# Dev_BRD_ATTINY1616.net
KiCad netlist of a schematic drawn in Altium Designer
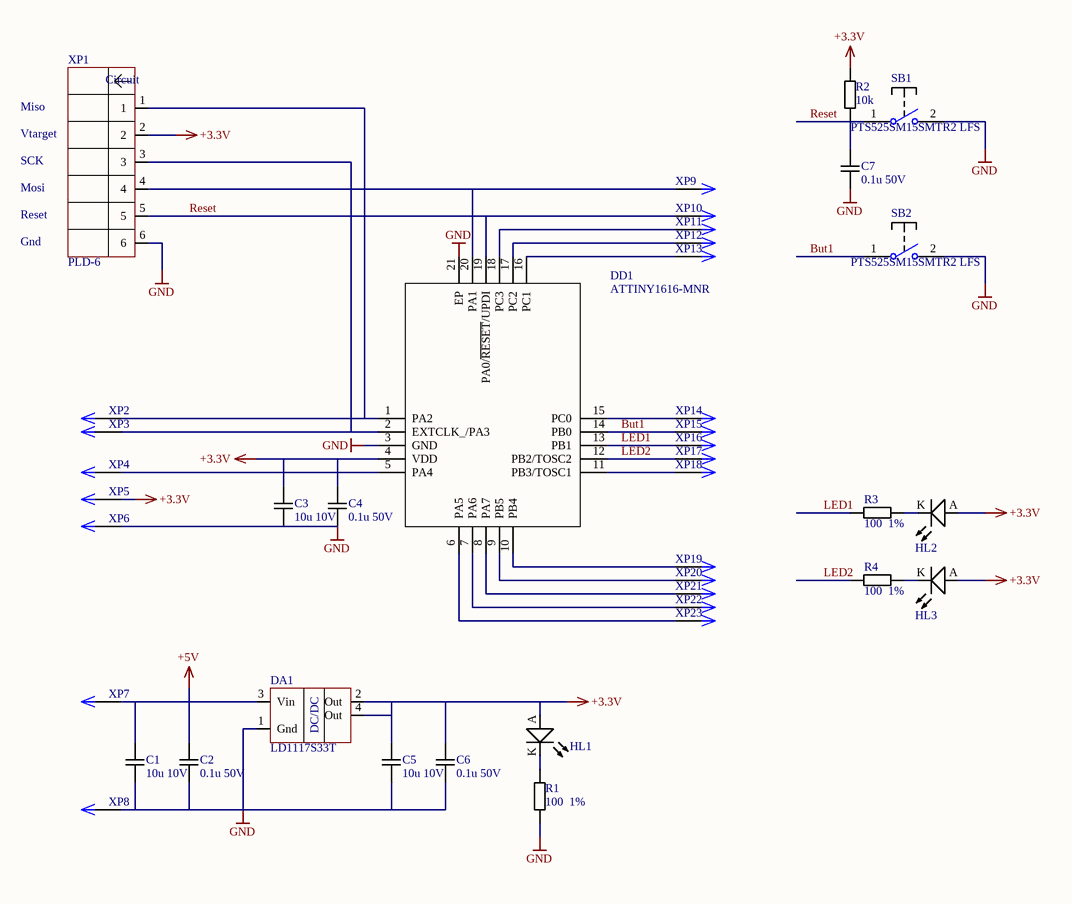
[diagram p0: Dev_BRD_ATTINY1616.SchDoc]

(export (version "E")
  (design (tool "Eeschema 10.0.6"))
  (components
    (comp (ref "C1")
      (value "10u 10V")
      (footprint "CAPC1608(0603)N")
      (description "10uF 0603 10V X5R  10%")
      (fields
        (field (name "PART NUMBER") "GRM188R61A106KE69J")
        (field (name "MOUSER PART NUMBER") "81-GRM188R61A106KE9J")
      )
      (libsource (lib "SssAccesDatbase") (part "Cap"))
    )
    (comp (ref "C2")
      (value "0.1u 50V")
      (footprint "CAPC1608(0603)N")
      (description "0,1uF 0603 50V X7R  +/-20%")
      (fields
        (field (name "PART NUMBER") "UMF107B7104MAHT")
        (field (name "MOUSER PART NUMBER") "963-UMF107B7104MAHT")
      )
      (libsource (lib "SssAccesDatbase") (part "Cap"))
    )
    (comp (ref "C3")
      (value "10u 10V")
      (footprint "CAPC1608(0603)N")
      (description "10uF 0603 10V X5R  10%")
      (fields
        (field (name "PART NUMBER") "GRM188R61A106KE69J")
        (field (name "MOUSER PART NUMBER") "81-GRM188R61A106KE9J")
      )
      (libsource (lib "SssAccesDatbase") (part "Cap"))
    )
    (comp (ref "C4")
      (value "0.1u 50V")
      (footprint "CAPC1608(0603)N")
      (description "0,1uF 0603 50V X7R  +/-20%")
      (fields
        (field (name "PART NUMBER") "UMF107B7104MAHT")
        (field (name "MOUSER PART NUMBER") "963-UMF107B7104MAHT")
      )
      (libsource (lib "SssAccesDatbase") (part "Cap"))
    )
    (comp (ref "C5")
      (value "10u 10V")
      (footprint "CAPC1608(0603)N")
      (description "10uF 0603 10V X5R  10%")
      (fields
        (field (name "PART NUMBER") "GRM188R61A106KE69J")
        (field (name "MOUSER PART NUMBER") "81-GRM188R61A106KE9J")
      )
      (libsource (lib "SssAccesDatbase") (part "Cap"))
    )
    (comp (ref "C6")
      (value "0.1u 50V")
      (footprint "CAPC1608(0603)N")
      (description "0,1uF 0603 50V X7R  +/-20%")
      (fields
        (field (name "PART NUMBER") "UMF107B7104MAHT")
        (field (name "MOUSER PART NUMBER") "963-UMF107B7104MAHT")
      )
      (libsource (lib "SssAccesDatbase") (part "Cap"))
    )
    (comp (ref "C7")
      (value "0.1u 50V")
      (footprint "CAPC1608(0603)N")
      (description "0,1uF 0603 50V X7R  +/-20%")
      (fields
        (field (name "PART NUMBER") "UMF107B7104MAHT")
        (field (name "MOUSER PART NUMBER") "963-UMF107B7104MAHT")
      )
      (libsource (lib "SssAccesDatbase") (part "Cap"))
    )
    (comp (ref "DA1")
      (value "LD1117S33T")
      (footprint "SOT223_M")
      (description "LDO Voltage Regulators 3.3V 0.8A Positive")
      (libsource (lib "SssAccesDatbase") (part "LD1117S33T"))
    )
    (comp (ref "DD1")
      (value "ATTINY1616-MNR")
      (footprint "QFN40P300X300X90-21N")
      (description "AVR tinyAVR™ 1 Microcontroller IC 8-Bit 20MHz 16KB (16K x 8) FLASH 20-VQFN (3x3)")
      (fields
        (field (name "MOUSER PART NUMBER") "556-ATTINY1616MNR")
        (field (name "DIGI-KEY PART NUMBER") "ATTINY1616-MNRCT-ND")
      )
      (libsource (lib "SssAccesDatbase") (part "ATTINY1616-MNR_1"))
    )
    (comp (ref "HL1")
      (value "Bl 0603")
      (footprint "LED-0603-BLUE")
      (description "LED BLUE DIFFUSED 0603 SMD")
      (fields
        (field (name "PART NUMBER") "150060BS55040")
        (field (name "DIGI-KEY PART NUMBER") "732-12013-1-ND")
      )
      (libsource (lib "SssAccesDatbase") (part "LED"))
    )
    (comp (ref "HL2")
      (value "Bl 0603")
      (footprint "LED-0603-BLUE")
      (description "LED BLUE DIFFUSED 0603 SMD")
      (fields
        (field (name "PART NUMBER") "150060BS55040")
        (field (name "DIGI-KEY PART NUMBER") "732-12013-1-ND")
      )
      (libsource (lib "SssAccesDatbase") (part "LED"))
    )
    (comp (ref "HL3")
      (value "Bl 0603")
      (footprint "LED-0603-BLUE")
      (description "LED BLUE DIFFUSED 0603 SMD")
      (fields
        (field (name "PART NUMBER") "150060BS55040")
        (field (name "DIGI-KEY PART NUMBER") "732-12013-1-ND")
      )
      (libsource (lib "SssAccesDatbase") (part "LED"))
    )
    (comp (ref "R1")
      (value "100  1%")
      (footprint "RESC1608(0603)N")
      (description "RES SMD 0603 100  1% 25ppm")
      (fields
        (field (name "PART NUMBER") "RT0603FRD07100RL")
        (field (name "MOUSER PART NUMBER") "603-RT0603FRD07100RL")
      )
      (libsource (lib "") (part "Resistor general_1"))
    )
    (comp (ref "R2")
      (value "10k")
      (footprint "RESC1608(0603)N")
      (description "RES SMD 0603 10k 5% 100ppm")
      (fields
        (field (name "PART NUMBER") "RC0603JR-0710KL")
        (field (name "MOUSER PART NUMBER") "603-RC0603JR-0710KL")
      )
      (libsource (lib "") (part "Resistor general_1"))
    )
    (comp (ref "R3")
      (value "100  1%")
      (footprint "RESC1608(0603)N")
      (description "RES SMD 0603 100  1% 25ppm")
      (fields
        (field (name "PART NUMBER") "RT0603FRD07100RL")
        (field (name "MOUSER PART NUMBER") "603-RT0603FRD07100RL")
      )
      (libsource (lib "SssAccesDatbase") (part "Resistor general"))
    )
    (comp (ref "R4")
      (value "100  1%")
      (footprint "RESC1608(0603)N")
      (description "RES SMD 0603 100  1% 25ppm")
      (fields
        (field (name "PART NUMBER") "RT0603FRD07100RL")
        (field (name "MOUSER PART NUMBER") "603-RT0603FRD07100RL")
      )
      (libsource (lib "SssAccesDatbase") (part "Resistor general"))
    )
    (comp (ref "SB1")
      (value "PTS525SM15SMTR2 LFS")
      (footprint "TACT_SWITCH KPT1187B")
      (description "SWITCH TACTILE SPST-NO 0.02A 15V")
      (fields (field (name "DIGI-KEY PART NUMBER") "CKN9104CT-ND"))
      (libsource (lib "SssAccesDatbase") (part "TACT_SWITCH KPT1187B"))
    )
    (comp (ref "SB2")
      (value "PTS525SM15SMTR2 LFS")
      (footprint "TACT_SWITCH KPT1187B")
      (description "SWITCH TACTILE SPST-NO 0.02A 15V")
      (fields (field (name "DIGI-KEY PART NUMBER") "CKN9104CT-ND"))
      (libsource (lib "SssAccesDatbase") (part "TACT_SWITCH KPT1187B"))
    )
    (comp (ref "XP1")
      (value "PLD-6")
      (footprint "PLD-6-3D")
      (libsource (lib "SssAccesDatbase") (part "XP-6"))
    )
    (comp (ref "XP2")
      (value "PLS-1")
      (footprint "PLS-1-3D")
      (description "CONN HEADER VERT 1POS")
      (fields
        (field (name "DIGI-KEY PART NUMBER") "S1011EC-01-ND")
        (field (name "MANUFACTURER PART NUMBER") "PRPC001SAAN-RC")
      )
      (libsource (lib "SssAccesDatbase") (part "XP-1_1"))
    )
    (comp (ref "XP3")
      (value "PLS-1")
      (footprint "PLS-1-3D")
      (description "CONN HEADER VERT 1POS")
      (fields
        (field (name "DIGI-KEY PART NUMBER") "S1011EC-01-ND")
        (field (name "MANUFACTURER PART NUMBER") "PRPC001SAAN-RC")
      )
      (libsource (lib "SssAccesDatbase") (part "XP-1_1"))
    )
    (comp (ref "XP4")
      (value "PLS-1")
      (footprint "PLS-1-3D")
      (description "CONN HEADER VERT 1POS")
      (fields
        (field (name "DIGI-KEY PART NUMBER") "S1011EC-01-ND")
        (field (name "MANUFACTURER PART NUMBER") "PRPC001SAAN-RC")
      )
      (libsource (lib "SssAccesDatbase") (part "XP-1_1"))
    )
    (comp (ref "XP5")
      (value "PLS-1")
      (footprint "PLS-1-3D")
      (description "CONN HEADER VERT 1POS")
      (fields
        (field (name "DIGI-KEY PART NUMBER") "S1011EC-01-ND")
        (field (name "MANUFACTURER PART NUMBER") "PRPC001SAAN-RC")
      )
      (libsource (lib "SssAccesDatbase") (part "XP-1_1"))
    )
    (comp (ref "XP6")
      (value "PLS-1")
      (footprint "PLS-1-3D")
      (description "CONN HEADER VERT 1POS")
      (fields
        (field (name "DIGI-KEY PART NUMBER") "S1011EC-01-ND")
        (field (name "MANUFACTURER PART NUMBER") "PRPC001SAAN-RC")
      )
      (libsource (lib "SssAccesDatbase") (part "XP-1_1"))
    )
    (comp (ref "XP7")
      (value "PLS-1")
      (footprint "PLS-1-3D")
      (description "CONN HEADER VERT 1POS")
      (fields
        (field (name "DIGI-KEY PART NUMBER") "S1011EC-01-ND")
        (field (name "MANUFACTURER PART NUMBER") "PRPC001SAAN-RC")
      )
      (libsource (lib "SssAccesDatbase") (part "XP-1_1"))
    )
    (comp (ref "XP8")
      (value "PLS-1")
      (footprint "PLS-1-3D")
      (description "CONN HEADER VERT 1POS")
      (fields
        (field (name "DIGI-KEY PART NUMBER") "S1011EC-01-ND")
        (field (name "MANUFACTURER PART NUMBER") "PRPC001SAAN-RC")
      )
      (libsource (lib "SssAccesDatbase") (part "XP-1_1"))
    )
    (comp (ref "XP9")
      (value "PLS-1")
      (footprint "PLS-1-3D")
      (description "CONN HEADER VERT 1POS")
      (fields
        (field (name "DIGI-KEY PART NUMBER") "S1011EC-01-ND")
        (field (name "MANUFACTURER PART NUMBER") "PRPC001SAAN-RC")
      )
      (libsource (lib "SssAccesDatbase") (part "XP-1_1"))
    )
    (comp (ref "XP10")
      (value "PLS-1")
      (footprint "PLS-1-3D")
      (description "CONN HEADER VERT 1POS")
      (fields
        (field (name "DIGI-KEY PART NUMBER") "S1011EC-01-ND")
        (field (name "MANUFACTURER PART NUMBER") "PRPC001SAAN-RC")
      )
      (libsource (lib "SssAccesDatbase") (part "XP-1_1"))
    )
    (comp (ref "XP11")
      (value "PLS-1")
      (footprint "PLS-1-3D")
      (description "CONN HEADER VERT 1POS")
      (fields
        (field (name "DIGI-KEY PART NUMBER") "S1011EC-01-ND")
        (field (name "MANUFACTURER PART NUMBER") "PRPC001SAAN-RC")
      )
      (libsource (lib "SssAccesDatbase") (part "XP-1_1"))
    )
    (comp (ref "XP12")
      (value "PLS-1")
      (footprint "PLS-1-3D")
      (description "CONN HEADER VERT 1POS")
      (fields
        (field (name "DIGI-KEY PART NUMBER") "S1011EC-01-ND")
        (field (name "MANUFACTURER PART NUMBER") "PRPC001SAAN-RC")
      )
      (libsource (lib "SssAccesDatbase") (part "XP-1_1"))
    )
    (comp (ref "XP13")
      (value "PLS-1")
      (footprint "PLS-1-3D")
      (description "CONN HEADER VERT 1POS")
      (fields
        (field (name "DIGI-KEY PART NUMBER") "S1011EC-01-ND")
        (field (name "MANUFACTURER PART NUMBER") "PRPC001SAAN-RC")
      )
      (libsource (lib "SssAccesDatbase") (part "XP-1_1"))
    )
    (comp (ref "XP14")
      (value "PLS-1")
      (footprint "PLS-1-3D")
      (description "CONN HEADER VERT 1POS")
      (fields
        (field (name "DIGI-KEY PART NUMBER") "S1011EC-01-ND")
        (field (name "MANUFACTURER PART NUMBER") "PRPC001SAAN-RC")
      )
      (libsource (lib "SssAccesDatbase") (part "XP-1_1"))
    )
    (comp (ref "XP15")
      (value "PLS-1")
      (footprint "PLS-1-3D")
      (description "CONN HEADER VERT 1POS")
      (fields
        (field (name "DIGI-KEY PART NUMBER") "S1011EC-01-ND")
        (field (name "MANUFACTURER PART NUMBER") "PRPC001SAAN-RC")
      )
      (libsource (lib "SssAccesDatbase") (part "XP-1_1"))
    )
    (comp (ref "XP16")
      (value "PLS-1")
      (footprint "PLS-1-3D")
      (description "CONN HEADER VERT 1POS")
      (fields
        (field (name "DIGI-KEY PART NUMBER") "S1011EC-01-ND")
        (field (name "MANUFACTURER PART NUMBER") "PRPC001SAAN-RC")
      )
      (libsource (lib "SssAccesDatbase") (part "XP-1_1"))
    )
    (comp (ref "XP17")
      (value "PLS-1")
      (footprint "PLS-1-3D")
      (description "CONN HEADER VERT 1POS")
      (fields
        (field (name "DIGI-KEY PART NUMBER") "S1011EC-01-ND")
        (field (name "MANUFACTURER PART NUMBER") "PRPC001SAAN-RC")
      )
      (libsource (lib "SssAccesDatbase") (part "XP-1_1"))
    )
    (comp (ref "XP18")
      (value "PLS-1")
      (footprint "PLS-1-3D")
      (description "CONN HEADER VERT 1POS")
      (fields
        (field (name "DIGI-KEY PART NUMBER") "S1011EC-01-ND")
        (field (name "MANUFACTURER PART NUMBER") "PRPC001SAAN-RC")
      )
      (libsource (lib "SssAccesDatbase") (part "XP-1_1"))
    )
    (comp (ref "XP19")
      (value "PLS-1")
      (footprint "PLS-1-3D")
      (description "CONN HEADER VERT 1POS")
      (fields
        (field (name "DIGI-KEY PART NUMBER") "S1011EC-01-ND")
        (field (name "MANUFACTURER PART NUMBER") "PRPC001SAAN-RC")
      )
      (libsource (lib "SssAccesDatbase") (part "XP-1_1"))
    )
    (comp (ref "XP20")
      (value "PLS-1")
      (footprint "PLS-1-3D")
      (description "CONN HEADER VERT 1POS")
      (fields
        (field (name "DIGI-KEY PART NUMBER") "S1011EC-01-ND")
        (field (name "MANUFACTURER PART NUMBER") "PRPC001SAAN-RC")
      )
      (libsource (lib "SssAccesDatbase") (part "XP-1_1"))
    )
    (comp (ref "XP21")
      (value "PLS-1")
      (footprint "PLS-1-3D")
      (description "CONN HEADER VERT 1POS")
      (fields
        (field (name "DIGI-KEY PART NUMBER") "S1011EC-01-ND")
        (field (name "MANUFACTURER PART NUMBER") "PRPC001SAAN-RC")
      )
      (libsource (lib "SssAccesDatbase") (part "XP-1_1"))
    )
    (comp (ref "XP22")
      (value "PLS-1")
      (footprint "PLS-1-3D")
      (description "CONN HEADER VERT 1POS")
      (fields
        (field (name "DIGI-KEY PART NUMBER") "S1011EC-01-ND")
        (field (name "MANUFACTURER PART NUMBER") "PRPC001SAAN-RC")
      )
      (libsource (lib "SssAccesDatbase") (part "XP-1_1"))
    )
    (comp (ref "XP23")
      (value "PLS-1")
      (footprint "PLS-1-3D")
      (description "CONN HEADER VERT 1POS")
      (fields
        (field (name "DIGI-KEY PART NUMBER") "S1011EC-01-ND")
        (field (name "MANUFACTURER PART NUMBER") "PRPC001SAAN-RC")
      )
      (libsource (lib "SssAccesDatbase") (part "XP-1_1"))
    )
  )
  (nets
    (net (code "1") (name "+3.3V") (class "Default")
      (node (ref "C3") (pin "2") (pinfunction "2_2") (pintype "passive"))
      (node (ref "C4") (pin "1") (pinfunction "1_1") (pintype "passive"))
      (node (ref "C5") (pin "2") (pinfunction "2_2") (pintype "passive"))
      (node (ref "C6") (pin "1") (pinfunction "1_1") (pintype "passive"))
      (node (ref "DA1") (pin "2") (pinfunction "Out_2") (pintype "passive"))
      (node (ref "DA1") (pin "4") (pinfunction "Out_4") (pintype "passive"))
      (node (ref "DD1") (pin "4") (pinfunction "VDD_4") (pintype "passive"))
      (node (ref "HL1") (pin "A") (pinfunction "A_A") (pintype "passive"))
      (node (ref "HL2") (pin "A") (pinfunction "A_A") (pintype "passive"))
      (node (ref "HL3") (pin "A") (pinfunction "A_A") (pintype "passive"))
      (node (ref "R2") (pin "2") (pinfunction "2_2") (pintype "passive"))
      (node (ref "XP1") (pin "2") (pinfunction "2_2") (pintype "passive"))
      (node (ref "XP5") (pin "1") (pinfunction "1_1") (pintype "passive"))
    )
    (net (code "2") (name "+5V") (class "Default")
      (node (ref "C1") (pin "2") (pinfunction "2_2") (pintype "passive"))
      (node (ref "C2") (pin "1") (pinfunction "1_1") (pintype "passive"))
      (node (ref "DA1") (pin "3") (pinfunction "Vin_3") (pintype "passive"))
      (node (ref "XP7") (pin "1") (pinfunction "1_1") (pintype "passive"))
    )
    (net (code "3") (name "/But1") (class "Default")
      (node (ref "DD1") (pin "14") (pinfunction "PB0_14") (pintype "passive"))
      (node (ref "SB2") (pin "1") (pinfunction "COMMON_1") (pintype "passive"))
      (node (ref "XP15") (pin "1") (pinfunction "1_1") (pintype "passive"))
    )
    (net (code "4") (name "/LED1") (class "Default")
      (node (ref "DD1") (pin "13") (pinfunction "PB1_13") (pintype "passive"))
      (node (ref "R3") (pin "2") (pinfunction "2_2") (pintype "passive"))
      (node (ref "XP16") (pin "1") (pinfunction "1_1") (pintype "passive"))
    )
    (net (code "5") (name "/LED2") (class "Default")
      (node (ref "DD1") (pin "12") (pinfunction "PB2/TOSC2_12") (pintype "passive"))
      (node (ref "R4") (pin "2") (pinfunction "2_2") (pintype "passive"))
      (node (ref "XP17") (pin "1") (pinfunction "1_1") (pintype "passive"))
    )
    (net (code "6") (name "/Reset") (class "Default")
      (node (ref "C7") (pin "1") (pinfunction "1_1") (pintype "passive"))
      (node (ref "DD1") (pin "19") (pinfunction "PA0/~{RESET}/UPDI_19") (pintype "passive"))
      (node (ref "R2") (pin "1") (pinfunction "1_1") (pintype "passive"))
      (node (ref "SB1") (pin "1") (pinfunction "COMMON_1") (pintype "passive"))
      (node (ref "XP1") (pin "5") (pinfunction "5_5") (pintype "passive"))
      (node (ref "XP10") (pin "1") (pinfunction "1_1") (pintype "passive"))
    )
    (net (code "7") (name "GND") (class "Default")
      (node (ref "C1") (pin "1") (pinfunction "1_1") (pintype "passive"))
      (node (ref "C2") (pin "2") (pinfunction "2_2") (pintype "passive"))
      (node (ref "C3") (pin "1") (pinfunction "1_1") (pintype "passive"))
      (node (ref "C4") (pin "2") (pinfunction "2_2") (pintype "passive"))
      (node (ref "C5") (pin "1") (pinfunction "1_1") (pintype "passive"))
      (node (ref "C6") (pin "2") (pinfunction "2_2") (pintype "passive"))
      (node (ref "C7") (pin "2") (pinfunction "2_2") (pintype "passive"))
      (node (ref "DA1") (pin "1") (pinfunction "Gnd_1") (pintype "passive"))
      (node (ref "DD1") (pin "21") (pinfunction "EP_21") (pintype "passive"))
      (node (ref "DD1") (pin "3") (pinfunction "GND_3") (pintype "passive"))
      (node (ref "R1") (pin "1") (pinfunction "1_1") (pintype "passive"))
      (node (ref "SB1") (pin "2") (pinfunction "NO_2") (pintype "passive"))
      (node (ref "SB2") (pin "2") (pinfunction "NO_2") (pintype "passive"))
      (node (ref "XP1") (pin "6") (pinfunction "6_6") (pintype "passive"))
      (node (ref "XP6") (pin "1") (pinfunction "1_1") (pintype "passive"))
      (node (ref "XP8") (pin "1") (pinfunction "1_1") (pintype "passive"))
    )
    (net (code "8") (name "Net-(DD1-EXTCLK_{slash}PA3)") (class "Default")
      (node (ref "DD1") (pin "2") (pinfunction "EXTCLK_/PA3_2") (pintype "passive"))
      (node (ref "XP1") (pin "3") (pinfunction "3_3") (pintype "passive"))
      (node (ref "XP3") (pin "1") (pinfunction "1_1") (pintype "passive"))
    )
    (net (code "9") (name "Net-(DD1-PA1)") (class "Default")
      (node (ref "DD1") (pin "20") (pinfunction "PA1_20") (pintype "passive"))
      (node (ref "XP1") (pin "4") (pinfunction "4_4") (pintype "passive"))
      (node (ref "XP9") (pin "1") (pinfunction "1_1") (pintype "passive"))
    )
    (net (code "10") (name "Net-(DD1-PA2)") (class "Default")
      (node (ref "DD1") (pin "1") (pinfunction "PA2_1") (pintype "passive"))
      (node (ref "XP1") (pin "1") (pinfunction "1_1") (pintype "passive"))
      (node (ref "XP2") (pin "1") (pinfunction "1_1") (pintype "passive"))
    )
    (net (code "11") (name "Net-(DD1-PA4)") (class "Default")
      (node (ref "DD1") (pin "5") (pinfunction "PA4_5") (pintype "passive"))
      (node (ref "XP4") (pin "1") (pinfunction "1_1") (pintype "passive"))
    )
    (net (code "12") (name "Net-(DD1-PA5)") (class "Default")
      (node (ref "DD1") (pin "6") (pinfunction "PA5_6") (pintype "passive"))
      (node (ref "XP23") (pin "1") (pinfunction "1_1") (pintype "passive"))
    )
    (net (code "13") (name "Net-(DD1-PA6)") (class "Default")
      (node (ref "DD1") (pin "7") (pinfunction "PA6_7") (pintype "passive"))
      (node (ref "XP22") (pin "1") (pinfunction "1_1") (pintype "passive"))
    )
    (net (code "14") (name "Net-(DD1-PA7)") (class "Default")
      (node (ref "DD1") (pin "8") (pinfunction "PA7_8") (pintype "passive"))
      (node (ref "XP21") (pin "1") (pinfunction "1_1") (pintype "passive"))
    )
    (net (code "15") (name "Net-(DD1-PB3{slash}TOSC1)") (class "Default")
      (node (ref "DD1") (pin "11") (pinfunction "PB3/TOSC1_11") (pintype "passive"))
      (node (ref "XP18") (pin "1") (pinfunction "1_1") (pintype "passive"))
    )
    (net (code "16") (name "Net-(DD1-PB4)") (class "Default")
      (node (ref "DD1") (pin "10") (pinfunction "PB4_10") (pintype "passive"))
      (node (ref "XP19") (pin "1") (pinfunction "1_1") (pintype "passive"))
    )
    (net (code "17") (name "Net-(DD1-PB5)") (class "Default")
      (node (ref "DD1") (pin "9") (pinfunction "PB5_9") (pintype "passive"))
      (node (ref "XP20") (pin "1") (pinfunction "1_1") (pintype "passive"))
    )
    (net (code "18") (name "Net-(DD1-PC0)") (class "Default")
      (node (ref "DD1") (pin "15") (pinfunction "PC0_15") (pintype "passive"))
      (node (ref "XP14") (pin "1") (pinfunction "1_1") (pintype "passive"))
    )
    (net (code "19") (name "Net-(DD1-PC1)") (class "Default")
      (node (ref "DD1") (pin "16") (pinfunction "PC1_16") (pintype "passive"))
      (node (ref "XP13") (pin "1") (pinfunction "1_1") (pintype "passive"))
    )
    (net (code "20") (name "Net-(DD1-PC2)") (class "Default")
      (node (ref "DD1") (pin "17") (pinfunction "PC2_17") (pintype "passive"))
      (node (ref "XP12") (pin "1") (pinfunction "1_1") (pintype "passive"))
    )
    (net (code "21") (name "Net-(DD1-PC3)") (class "Default")
      (node (ref "DD1") (pin "18") (pinfunction "PC3_18") (pintype "passive"))
      (node (ref "XP11") (pin "1") (pinfunction "1_1") (pintype "passive"))
    )
    (net (code "22") (name "Net-(HL1-PadK)") (class "Default")
      (node (ref "HL1") (pin "K") (pinfunction "K_K") (pintype "passive"))
      (node (ref "R1") (pin "2") (pinfunction "2_2") (pintype "passive"))
    )
    (net (code "23") (name "Net-(HL2-PadK)") (class "Default")
      (node (ref "HL2") (pin "K") (pinfunction "K_K") (pintype "passive"))
      (node (ref "R3") (pin "1") (pinfunction "1_1") (pintype "passive"))
    )
    (net (code "24") (name "Net-(HL3-PadK)") (class "Default")
      (node (ref "HL3") (pin "K") (pinfunction "K_K") (pintype "passive"))
      (node (ref "R4") (pin "1") (pinfunction "1_1") (pintype "passive"))
    )
  )
)
